# Sheet.net
KiCad netlist of a schematic drawn in Altium Designer
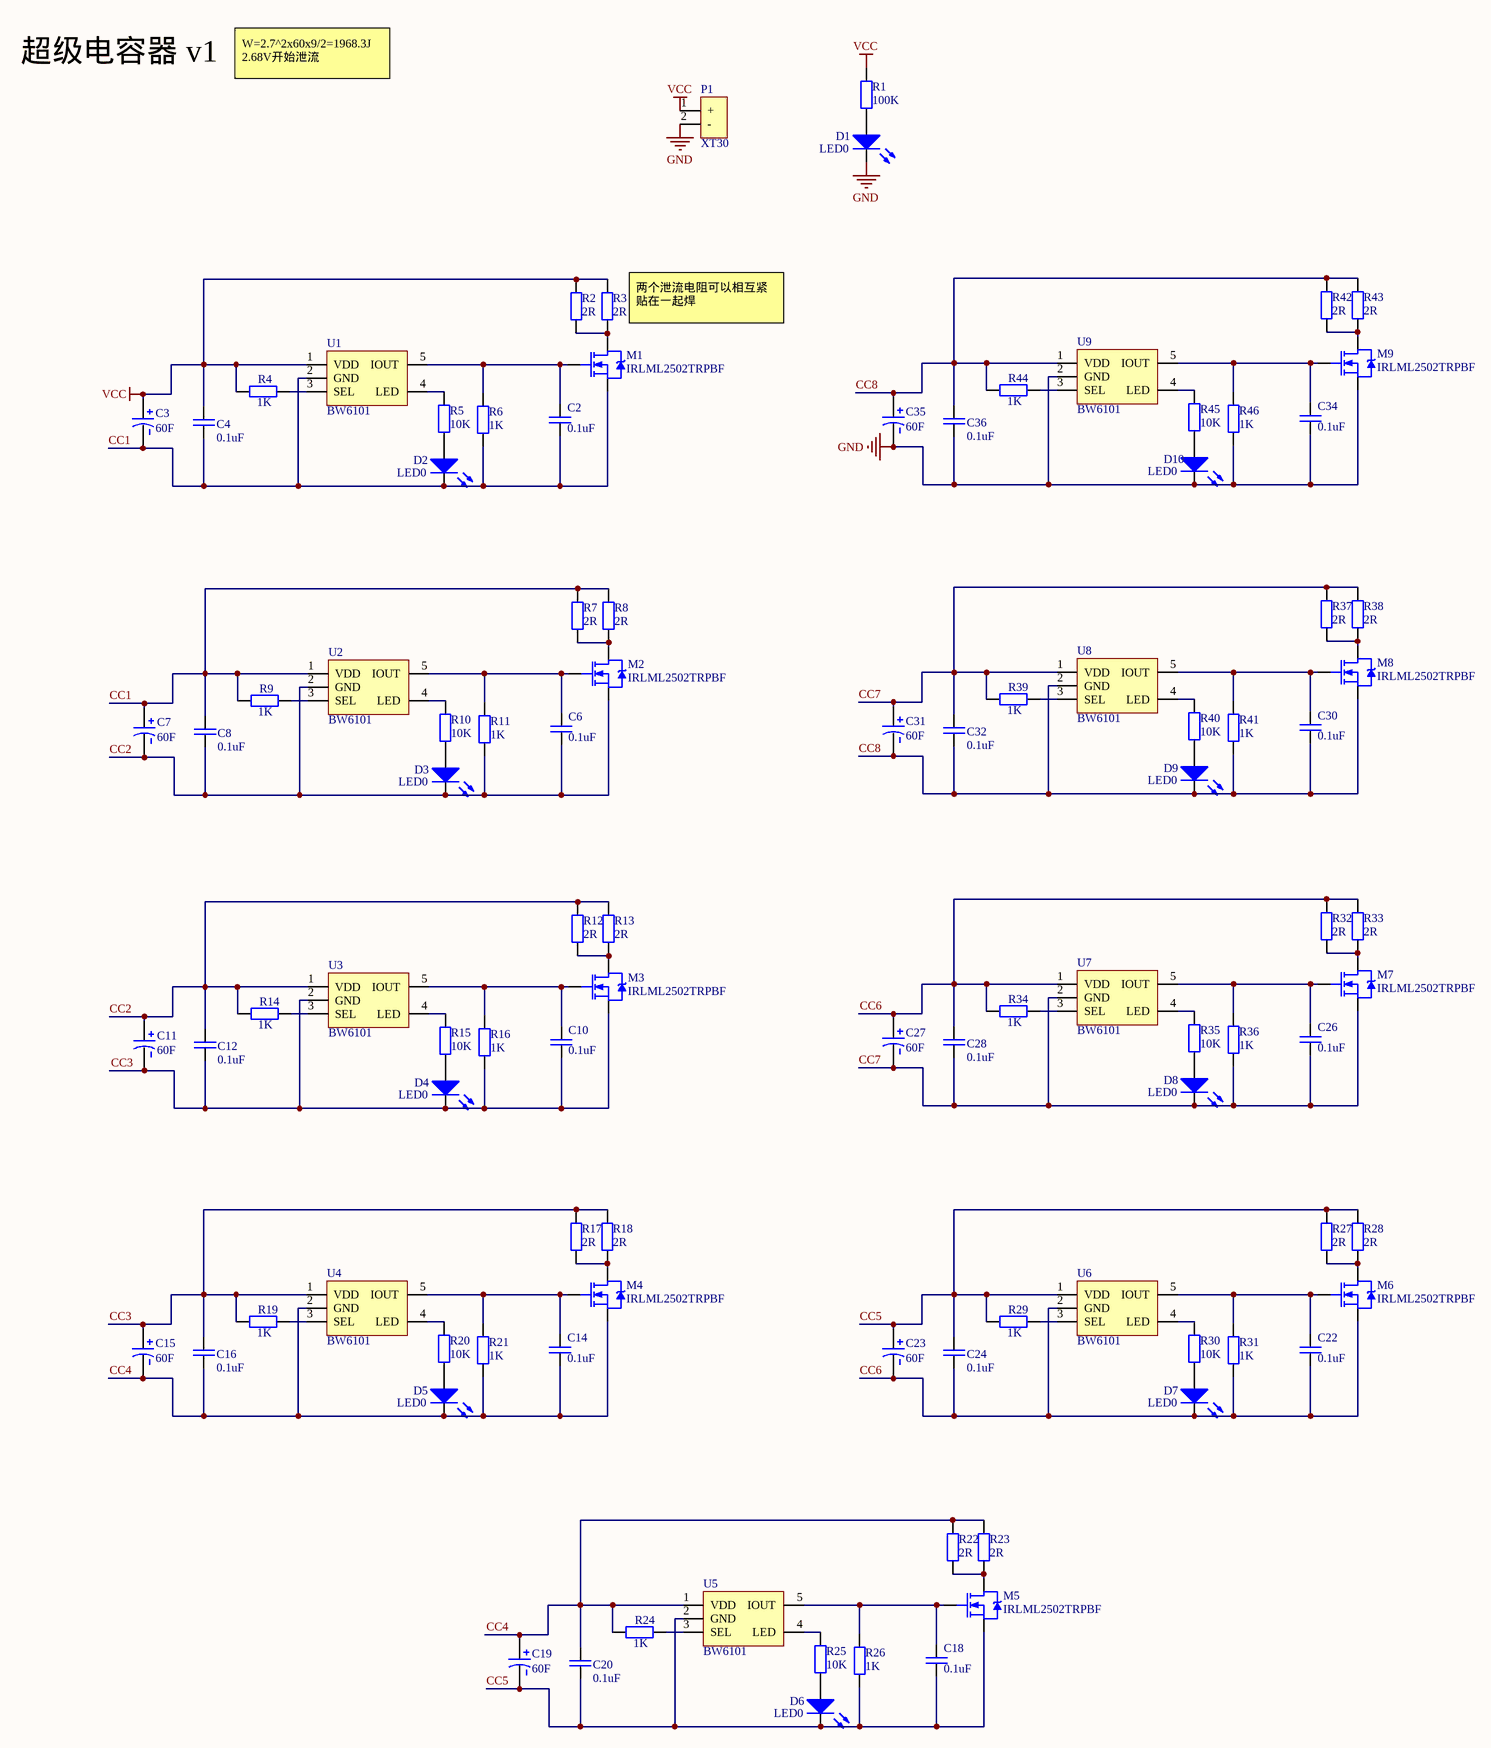
[diagram p0: Sheet.SchDoc]

(export (version "E")
  (design (tool "Eeschema 10.0.6"))
  (components
    (comp (ref "C2")
      (value "0.1uF")
      (footprint "0603_C")
      (fields (field (name "PUBLISHER") "Altium Limited"))
      (libsource (lib "电容-电阻-电感") (part "Cap"))
    )
    (comp (ref "C3") (value "60F") (footprint "18x40mm") (libsource (lib "电容-电阻-电感") (part "Super Cap")))
    (comp (ref "C4")
      (value "0.1uF")
      (footprint "0603_C")
      (fields (field (name "PUBLISHER") "Altium Limited"))
      (libsource (lib "电容-电阻-电感") (part "Cap"))
    )
    (comp (ref "C6")
      (value "0.1uF")
      (footprint "0603_C")
      (fields (field (name "PUBLISHER") "Altium Limited"))
      (libsource (lib "电容-电阻-电感") (part "Cap"))
    )
    (comp (ref "C7") (value "60F") (footprint "18x40mm") (libsource (lib "电容-电阻-电感") (part "Super Cap")))
    (comp (ref "C8")
      (value "0.1uF")
      (footprint "0603_C")
      (fields (field (name "PUBLISHER") "Altium Limited"))
      (libsource (lib "电容-电阻-电感") (part "Cap"))
    )
    (comp (ref "C10")
      (value "0.1uF")
      (footprint "0603_C")
      (fields (field (name "PUBLISHER") "Altium Limited"))
      (libsource (lib "电容-电阻-电感") (part "Cap"))
    )
    (comp (ref "C11") (value "60F") (footprint "18x40mm") (libsource (lib "电容-电阻-电感") (part "Super Cap")))
    (comp (ref "C12")
      (value "0.1uF")
      (footprint "0603_C")
      (fields (field (name "PUBLISHER") "Altium Limited"))
      (libsource (lib "电容-电阻-电感") (part "Cap"))
    )
    (comp (ref "C14")
      (value "0.1uF")
      (footprint "0603_C")
      (fields (field (name "PUBLISHER") "Altium Limited"))
      (libsource (lib "电容-电阻-电感") (part "Cap"))
    )
    (comp (ref "C15") (value "60F") (footprint "18x40mm") (libsource (lib "电容-电阻-电感") (part "Super Cap")))
    (comp (ref "C16")
      (value "0.1uF")
      (footprint "0603_C")
      (fields (field (name "PUBLISHER") "Altium Limited"))
      (libsource (lib "电容-电阻-电感") (part "Cap"))
    )
    (comp (ref "C18")
      (value "0.1uF")
      (footprint "0603_C")
      (fields (field (name "PUBLISHER") "Altium Limited"))
      (libsource (lib "电容-电阻-电感") (part "Cap"))
    )
    (comp (ref "C19") (value "60F") (footprint "18x40mm") (libsource (lib "电容-电阻-电感") (part "Super Cap")))
    (comp (ref "C20")
      (value "0.1uF")
      (footprint "0603_C")
      (fields (field (name "PUBLISHER") "Altium Limited"))
      (libsource (lib "电容-电阻-电感") (part "Cap"))
    )
    (comp (ref "C22")
      (value "0.1uF")
      (footprint "0603_C")
      (fields (field (name "PUBLISHER") "Altium Limited"))
      (libsource (lib "电容-电阻-电感") (part "Cap"))
    )
    (comp (ref "C23") (value "60F") (footprint "18x40mm") (libsource (lib "电容-电阻-电感") (part "Super Cap")))
    (comp (ref "C24")
      (value "0.1uF")
      (footprint "0603_C")
      (fields (field (name "PUBLISHER") "Altium Limited"))
      (libsource (lib "电容-电阻-电感") (part "Cap"))
    )
    (comp (ref "C26")
      (value "0.1uF")
      (footprint "0603_C")
      (fields (field (name "PUBLISHER") "Altium Limited"))
      (libsource (lib "电容-电阻-电感") (part "Cap"))
    )
    (comp (ref "C27") (value "60F") (footprint "18x40mm") (libsource (lib "电容-电阻-电感") (part "Super Cap")))
    (comp (ref "C28")
      (value "0.1uF")
      (footprint "0603_C")
      (fields (field (name "PUBLISHER") "Altium Limited"))
      (libsource (lib "电容-电阻-电感") (part "Cap"))
    )
    (comp (ref "C30")
      (value "0.1uF")
      (footprint "0603_C")
      (fields (field (name "PUBLISHER") "Altium Limited"))
      (libsource (lib "电容-电阻-电感") (part "Cap"))
    )
    (comp (ref "C31") (value "60F") (footprint "18x40mm") (libsource (lib "电容-电阻-电感") (part "Super Cap")))
    (comp (ref "C32")
      (value "0.1uF")
      (footprint "0603_C")
      (fields (field (name "PUBLISHER") "Altium Limited"))
      (libsource (lib "电容-电阻-电感") (part "Cap"))
    )
    (comp (ref "C34")
      (value "0.1uF")
      (footprint "0603_C")
      (fields (field (name "PUBLISHER") "Altium Limited"))
      (libsource (lib "电容-电阻-电感") (part "Cap"))
    )
    (comp (ref "C35") (value "60F") (footprint "18x40mm") (libsource (lib "电容-电阻-电感") (part "Super Cap")))
    (comp (ref "C36")
      (value "0.1uF")
      (footprint "0603_C")
      (fields (field (name "PUBLISHER") "Altium Limited"))
      (libsource (lib "电容-电阻-电感") (part "Cap"))
    )
    (comp (ref "D1")
      (value "LED0")
      (footprint "LED-0603")
      (description "发光二极管")
      (fields (field (name "PUBLISHER") "Altium Limited"))
      (libsource (lib "晶体管") (part "LED0"))
    )
    (comp (ref "D2")
      (value "LED0")
      (footprint "LED-0603")
      (description "发光二极管")
      (fields (field (name "PUBLISHER") "Altium Limited"))
      (libsource (lib "晶体管") (part "LED0"))
    )
    (comp (ref "D3")
      (value "LED0")
      (footprint "LED-0603")
      (description "发光二极管")
      (fields (field (name "PUBLISHER") "Altium Limited"))
      (libsource (lib "晶体管") (part "LED0"))
    )
    (comp (ref "D4")
      (value "LED0")
      (footprint "LED-0603")
      (description "发光二极管")
      (fields (field (name "PUBLISHER") "Altium Limited"))
      (libsource (lib "晶体管") (part "LED0"))
    )
    (comp (ref "D5")
      (value "LED0")
      (footprint "LED-0603")
      (description "发光二极管")
      (fields (field (name "PUBLISHER") "Altium Limited"))
      (libsource (lib "晶体管") (part "LED0"))
    )
    (comp (ref "D6")
      (value "LED0")
      (footprint "LED-0603")
      (description "发光二极管")
      (fields (field (name "PUBLISHER") "Altium Limited"))
      (libsource (lib "晶体管") (part "LED0"))
    )
    (comp (ref "D7")
      (value "LED0")
      (footprint "LED-0603")
      (description "发光二极管")
      (fields (field (name "PUBLISHER") "Altium Limited"))
      (libsource (lib "晶体管") (part "LED0"))
    )
    (comp (ref "D8")
      (value "LED0")
      (footprint "LED-0603")
      (description "发光二极管")
      (fields (field (name "PUBLISHER") "Altium Limited"))
      (libsource (lib "晶体管") (part "LED0"))
    )
    (comp (ref "D9")
      (value "LED0")
      (footprint "LED-0603")
      (description "发光二极管")
      (fields (field (name "PUBLISHER") "Altium Limited"))
      (libsource (lib "晶体管") (part "LED0"))
    )
    (comp (ref "D10")
      (value "LED0")
      (footprint "LED-0603")
      (description "发光二极管")
      (fields (field (name "PUBLISHER") "Altium Limited"))
      (libsource (lib "晶体管") (part "LED0"))
    )
    (comp (ref "M1")
      (value "IRLML2502TRPBF")
      (footprint "SOT_23 mos")
      (libsource (lib "晶体管") (part "MOSFET"))
    )
    (comp (ref "M2")
      (value "IRLML2502TRPBF")
      (footprint "SOT_23 mos")
      (libsource (lib "晶体管") (part "MOSFET"))
    )
    (comp (ref "M3")
      (value "IRLML2502TRPBF")
      (footprint "SOT_23 mos")
      (libsource (lib "晶体管") (part "MOSFET"))
    )
    (comp (ref "M4")
      (value "IRLML2502TRPBF")
      (footprint "SOT_23 mos")
      (libsource (lib "晶体管") (part "MOSFET"))
    )
    (comp (ref "M5")
      (value "IRLML2502TRPBF")
      (footprint "SOT_23 mos")
      (libsource (lib "晶体管") (part "MOSFET"))
    )
    (comp (ref "M6")
      (value "IRLML2502TRPBF")
      (footprint "SOT_23 mos")
      (libsource (lib "晶体管") (part "MOSFET"))
    )
    (comp (ref "M7")
      (value "IRLML2502TRPBF")
      (footprint "SOT_23 mos")
      (libsource (lib "晶体管") (part "MOSFET"))
    )
    (comp (ref "M8")
      (value "IRLML2502TRPBF")
      (footprint "SOT_23 mos")
      (libsource (lib "晶体管") (part "MOSFET"))
    )
    (comp (ref "M9")
      (value "IRLML2502TRPBF")
      (footprint "SOT_23 mos")
      (libsource (lib "晶体管") (part "MOSFET"))
    )
    (comp (ref "P1") (value "XT30") (footprint "XT30-F") (libsource (lib "连接器") (part "XT30")))
    (comp (ref "R1")
      (value "100K")
      (footprint "0603_R")
      (fields (field (name "PUBLISHER") "Altium Limited"))
      (libsource (lib "电容-电阻-电感") (part "Res"))
    )
    (comp (ref "R2")
      (value "2R")
      (footprint "2512_R")
      (fields (field (name "PUBLISHER") "Altium Limited"))
      (libsource (lib "电容-电阻-电感") (part "Res"))
    )
    (comp (ref "R3")
      (value "2R")
      (footprint "2512_R")
      (fields (field (name "PUBLISHER") "Altium Limited"))
      (libsource (lib "电容-电阻-电感") (part "Res"))
    )
    (comp (ref "R4")
      (value "1K")
      (footprint "0603_R")
      (fields (field (name "PUBLISHER") "Altium Limited"))
      (libsource (lib "") (part "Res_1"))
    )
    (comp (ref "R5")
      (value "10K")
      (footprint "0603_R")
      (fields (field (name "PUBLISHER") "Altium Limited"))
      (libsource (lib "电容-电阻-电感") (part "Res"))
    )
    (comp (ref "R6")
      (value "1K")
      (footprint "0603_R")
      (fields (field (name "PUBLISHER") "Altium Limited"))
      (libsource (lib "电容-电阻-电感") (part "Res"))
    )
    (comp (ref "R7")
      (value "2R")
      (footprint "2512_R")
      (fields (field (name "PUBLISHER") "Altium Limited"))
      (libsource (lib "电容-电阻-电感") (part "Res"))
    )
    (comp (ref "R8")
      (value "2R")
      (footprint "2512_R")
      (fields (field (name "PUBLISHER") "Altium Limited"))
      (libsource (lib "电容-电阻-电感") (part "Res"))
    )
    (comp (ref "R9")
      (value "1K")
      (footprint "0603_R")
      (fields (field (name "PUBLISHER") "Altium Limited"))
      (libsource (lib "") (part "Res_1"))
    )
    (comp (ref "R10")
      (value "10K")
      (footprint "0603_R")
      (fields (field (name "PUBLISHER") "Altium Limited"))
      (libsource (lib "电容-电阻-电感") (part "Res"))
    )
    (comp (ref "R11")
      (value "1K")
      (footprint "0603_R")
      (fields (field (name "PUBLISHER") "Altium Limited"))
      (libsource (lib "电容-电阻-电感") (part "Res"))
    )
    (comp (ref "R12")
      (value "2R")
      (footprint "2512_R")
      (fields (field (name "PUBLISHER") "Altium Limited"))
      (libsource (lib "电容-电阻-电感") (part "Res"))
    )
    (comp (ref "R13")
      (value "2R")
      (footprint "2512_R")
      (fields (field (name "PUBLISHER") "Altium Limited"))
      (libsource (lib "电容-电阻-电感") (part "Res"))
    )
    (comp (ref "R14")
      (value "1K")
      (footprint "0603_R")
      (fields (field (name "PUBLISHER") "Altium Limited"))
      (libsource (lib "") (part "Res_1"))
    )
    (comp (ref "R15")
      (value "10K")
      (footprint "0603_R")
      (fields (field (name "PUBLISHER") "Altium Limited"))
      (libsource (lib "电容-电阻-电感") (part "Res"))
    )
    (comp (ref "R16")
      (value "1K")
      (footprint "0603_R")
      (fields (field (name "PUBLISHER") "Altium Limited"))
      (libsource (lib "电容-电阻-电感") (part "Res"))
    )
    (comp (ref "R17")
      (value "2R")
      (footprint "2512_R")
      (fields (field (name "PUBLISHER") "Altium Limited"))
      (libsource (lib "电容-电阻-电感") (part "Res"))
    )
    (comp (ref "R18")
      (value "2R")
      (footprint "2512_R")
      (fields (field (name "PUBLISHER") "Altium Limited"))
      (libsource (lib "电容-电阻-电感") (part "Res"))
    )
    (comp (ref "R19")
      (value "1K")
      (footprint "0603_R")
      (fields (field (name "PUBLISHER") "Altium Limited"))
      (libsource (lib "") (part "Res_1"))
    )
    (comp (ref "R20")
      (value "10K")
      (footprint "0603_R")
      (fields (field (name "PUBLISHER") "Altium Limited"))
      (libsource (lib "电容-电阻-电感") (part "Res"))
    )
    (comp (ref "R21")
      (value "1K")
      (footprint "0603_R")
      (fields (field (name "PUBLISHER") "Altium Limited"))
      (libsource (lib "电容-电阻-电感") (part "Res"))
    )
    (comp (ref "R22")
      (value "2R")
      (footprint "2512_R")
      (fields (field (name "PUBLISHER") "Altium Limited"))
      (libsource (lib "电容-电阻-电感") (part "Res"))
    )
    (comp (ref "R23")
      (value "2R")
      (footprint "2512_R")
      (fields (field (name "PUBLISHER") "Altium Limited"))
      (libsource (lib "电容-电阻-电感") (part "Res"))
    )
    (comp (ref "R24")
      (value "1K")
      (footprint "0603_R")
      (fields (field (name "PUBLISHER") "Altium Limited"))
      (libsource (lib "") (part "Res_1"))
    )
    (comp (ref "R25")
      (value "10K")
      (footprint "0603_R")
      (fields (field (name "PUBLISHER") "Altium Limited"))
      (libsource (lib "电容-电阻-电感") (part "Res"))
    )
    (comp (ref "R26")
      (value "1K")
      (footprint "0603_R")
      (fields (field (name "PUBLISHER") "Altium Limited"))
      (libsource (lib "电容-电阻-电感") (part "Res"))
    )
    (comp (ref "R27")
      (value "2R")
      (footprint "2512_R")
      (fields (field (name "PUBLISHER") "Altium Limited"))
      (libsource (lib "电容-电阻-电感") (part "Res"))
    )
    (comp (ref "R28")
      (value "2R")
      (footprint "2512_R")
      (fields (field (name "PUBLISHER") "Altium Limited"))
      (libsource (lib "电容-电阻-电感") (part "Res"))
    )
    (comp (ref "R29")
      (value "1K")
      (footprint "0603_R")
      (fields (field (name "PUBLISHER") "Altium Limited"))
      (libsource (lib "") (part "Res_1"))
    )
    (comp (ref "R30")
      (value "10K")
      (footprint "0603_R")
      (fields (field (name "PUBLISHER") "Altium Limited"))
      (libsource (lib "电容-电阻-电感") (part "Res"))
    )
    (comp (ref "R31")
      (value "1K")
      (footprint "0603_R")
      (fields (field (name "PUBLISHER") "Altium Limited"))
      (libsource (lib "电容-电阻-电感") (part "Res"))
    )
    (comp (ref "R32")
      (value "2R")
      (footprint "2512_R")
      (fields (field (name "PUBLISHER") "Altium Limited"))
      (libsource (lib "电容-电阻-电感") (part "Res"))
    )
    (comp (ref "R33")
      (value "2R")
      (footprint "2512_R")
      (fields (field (name "PUBLISHER") "Altium Limited"))
      (libsource (lib "电容-电阻-电感") (part "Res"))
    )
    (comp (ref "R34")
      (value "1K")
      (footprint "0603_R")
      (fields (field (name "PUBLISHER") "Altium Limited"))
      (libsource (lib "") (part "Res_1"))
    )
    (comp (ref "R35")
      (value "10K")
      (footprint "0603_R")
      (fields (field (name "PUBLISHER") "Altium Limited"))
      (libsource (lib "电容-电阻-电感") (part "Res"))
    )
    (comp (ref "R36")
      (value "1K")
      (footprint "0603_R")
      (fields (field (name "PUBLISHER") "Altium Limited"))
      (libsource (lib "电容-电阻-电感") (part "Res"))
    )
    (comp (ref "R37")
      (value "2R")
      (footprint "2512_R")
      (fields (field (name "PUBLISHER") "Altium Limited"))
      (libsource (lib "电容-电阻-电感") (part "Res"))
    )
    (comp (ref "R38")
      (value "2R")
      (footprint "2512_R")
      (fields (field (name "PUBLISHER") "Altium Limited"))
      (libsource (lib "电容-电阻-电感") (part "Res"))
    )
    (comp (ref "R39")
      (value "1K")
      (footprint "0603_R")
      (fields (field (name "PUBLISHER") "Altium Limited"))
      (libsource (lib "") (part "Res_1"))
    )
    (comp (ref "R40")
      (value "10K")
      (footprint "0603_R")
      (fields (field (name "PUBLISHER") "Altium Limited"))
      (libsource (lib "电容-电阻-电感") (part "Res"))
    )
    (comp (ref "R41")
      (value "1K")
      (footprint "0603_R")
      (fields (field (name "PUBLISHER") "Altium Limited"))
      (libsource (lib "电容-电阻-电感") (part "Res"))
    )
    (comp (ref "R42")
      (value "2R")
      (footprint "2512_R")
      (fields (field (name "PUBLISHER") "Altium Limited"))
      (libsource (lib "电容-电阻-电感") (part "Res"))
    )
    (comp (ref "R43")
      (value "2R")
      (footprint "2512_R")
      (fields (field (name "PUBLISHER") "Altium Limited"))
      (libsource (lib "电容-电阻-电感") (part "Res"))
    )
    (comp (ref "R44")
      (value "1K")
      (footprint "0603_R")
      (fields (field (name "PUBLISHER") "Altium Limited"))
      (libsource (lib "") (part "Res_1"))
    )
    (comp (ref "R45")
      (value "10K")
      (footprint "0603_R")
      (fields (field (name "PUBLISHER") "Altium Limited"))
      (libsource (lib "电容-电阻-电感") (part "Res"))
    )
    (comp (ref "R46")
      (value "1K")
      (footprint "0603_R")
      (fields (field (name "PUBLISHER") "Altium Limited"))
      (libsource (lib "电容-电阻-电感") (part "Res"))
    )
    (comp (ref "U1") (value "BW6101") (footprint "SOT23-5") (libsource (lib "Super Cap") (part "BW6101")))
    (comp (ref "U2") (value "BW6101") (footprint "SOT23-5") (libsource (lib "Super Cap") (part "BW6101")))
    (comp (ref "U3") (value "BW6101") (footprint "SOT23-5") (libsource (lib "Super Cap") (part "BW6101")))
    (comp (ref "U4") (value "BW6101") (footprint "SOT23-5") (libsource (lib "Super Cap") (part "BW6101")))
    (comp (ref "U5") (value "BW6101") (footprint "SOT23-5") (libsource (lib "Super Cap") (part "BW6101")))
    (comp (ref "U6") (value "BW6101") (footprint "SOT23-5") (libsource (lib "Super Cap") (part "BW6101")))
    (comp (ref "U7") (value "BW6101") (footprint "SOT23-5") (libsource (lib "Super Cap") (part "BW6101")))
    (comp (ref "U8") (value "BW6101") (footprint "SOT23-5") (libsource (lib "Super Cap") (part "BW6101")))
    (comp (ref "U9") (value "BW6101") (footprint "SOT23-5") (libsource (lib "Super Cap") (part "BW6101")))
  )
  (nets
    (net (code "1") (name "/CC1") (class "Default")
      (node (ref "C2") (pin "1") (pinfunction "1_1") (pintype "passive"))
      (node (ref "C3") (pin "2") (pinfunction "2_2") (pintype "passive"))
      (node (ref "C4") (pin "1") (pinfunction "1_1") (pintype "passive"))
      (node (ref "C7") (pin "1") (pinfunction "1_1") (pintype "passive"))
      (node (ref "C8") (pin "2") (pinfunction "2_2") (pintype "passive"))
      (node (ref "D2") (pin "2") (pinfunction "K_2") (pintype "passive"))
      (node (ref "M1") (pin "S") (pinfunction "S_S") (pintype "passive"))
      (node (ref "R6") (pin "1") (pinfunction "1_1") (pintype "passive"))
      (node (ref "R7") (pin "2") (pinfunction "2_2") (pintype "passive"))
      (node (ref "R8") (pin "2") (pinfunction "2_2") (pintype "passive"))
      (node (ref "R9") (pin "2") (pinfunction "2_2") (pintype "passive"))
      (node (ref "U1") (pin "2") (pinfunction "GND_2") (pintype "power_in"))
      (node (ref "U2") (pin "1") (pinfunction "VDD_1") (pintype "power_in"))
    )
    (net (code "2") (name "/CC2") (class "Default")
      (node (ref "C11") (pin "1") (pinfunction "1_1") (pintype "passive"))
      (node (ref "C12") (pin "2") (pinfunction "2_2") (pintype "passive"))
      (node (ref "C6") (pin "1") (pinfunction "1_1") (pintype "passive"))
      (node (ref "C7") (pin "2") (pinfunction "2_2") (pintype "passive"))
      (node (ref "C8") (pin "1") (pinfunction "1_1") (pintype "passive"))
      (node (ref "D3") (pin "2") (pinfunction "K_2") (pintype "passive"))
      (node (ref "M2") (pin "S") (pinfunction "S_S") (pintype "passive"))
      (node (ref "R11") (pin "1") (pinfunction "1_1") (pintype "passive"))
      (node (ref "R12") (pin "2") (pinfunction "2_2") (pintype "passive"))
      (node (ref "R13") (pin "2") (pinfunction "2_2") (pintype "passive"))
      (node (ref "R14") (pin "2") (pinfunction "2_2") (pintype "passive"))
      (node (ref "U2") (pin "2") (pinfunction "GND_2") (pintype "power_in"))
      (node (ref "U3") (pin "1") (pinfunction "VDD_1") (pintype "power_in"))
    )
    (net (code "3") (name "/CC3") (class "Default")
      (node (ref "C10") (pin "1") (pinfunction "1_1") (pintype "passive"))
      (node (ref "C11") (pin "2") (pinfunction "2_2") (pintype "passive"))
      (node (ref "C12") (pin "1") (pinfunction "1_1") (pintype "passive"))
      (node (ref "C15") (pin "1") (pinfunction "1_1") (pintype "passive"))
      (node (ref "C16") (pin "2") (pinfunction "2_2") (pintype "passive"))
      (node (ref "D4") (pin "2") (pinfunction "K_2") (pintype "passive"))
      (node (ref "M3") (pin "S") (pinfunction "S_S") (pintype "passive"))
      (node (ref "R16") (pin "1") (pinfunction "1_1") (pintype "passive"))
      (node (ref "R17") (pin "2") (pinfunction "2_2") (pintype "passive"))
      (node (ref "R18") (pin "2") (pinfunction "2_2") (pintype "passive"))
      (node (ref "R19") (pin "2") (pinfunction "2_2") (pintype "passive"))
      (node (ref "U3") (pin "2") (pinfunction "GND_2") (pintype "power_in"))
      (node (ref "U4") (pin "1") (pinfunction "VDD_1") (pintype "power_in"))
    )
    (net (code "4") (name "/CC4") (class "Default")
      (node (ref "C14") (pin "1") (pinfunction "1_1") (pintype "passive"))
      (node (ref "C15") (pin "2") (pinfunction "2_2") (pintype "passive"))
      (node (ref "C16") (pin "1") (pinfunction "1_1") (pintype "passive"))
      (node (ref "C19") (pin "1") (pinfunction "1_1") (pintype "passive"))
      (node (ref "C20") (pin "2") (pinfunction "2_2") (pintype "passive"))
      (node (ref "D5") (pin "2") (pinfunction "K_2") (pintype "passive"))
      (node (ref "M4") (pin "S") (pinfunction "S_S") (pintype "passive"))
      (node (ref "R21") (pin "1") (pinfunction "1_1") (pintype "passive"))
      (node (ref "R22") (pin "2") (pinfunction "2_2") (pintype "passive"))
      (node (ref "R23") (pin "2") (pinfunction "2_2") (pintype "passive"))
      (node (ref "R24") (pin "2") (pinfunction "2_2") (pintype "passive"))
      (node (ref "U4") (pin "2") (pinfunction "GND_2") (pintype "power_in"))
      (node (ref "U5") (pin "1") (pinfunction "VDD_1") (pintype "power_in"))
    )
    (net (code "5") (name "/CC5") (class "Default")
      (node (ref "C18") (pin "1") (pinfunction "1_1") (pintype "passive"))
      (node (ref "C19") (pin "2") (pinfunction "2_2") (pintype "passive"))
      (node (ref "C20") (pin "1") (pinfunction "1_1") (pintype "passive"))
      (node (ref "C23") (pin "1") (pinfunction "1_1") (pintype "passive"))
      (node (ref "C24") (pin "2") (pinfunction "2_2") (pintype "passive"))
      (node (ref "D6") (pin "2") (pinfunction "K_2") (pintype "passive"))
      (node (ref "M5") (pin "S") (pinfunction "S_S") (pintype "passive"))
      (node (ref "R26") (pin "1") (pinfunction "1_1") (pintype "passive"))
      (node (ref "R27") (pin "2") (pinfunction "2_2") (pintype "passive"))
      (node (ref "R28") (pin "2") (pinfunction "2_2") (pintype "passive"))
      (node (ref "R29") (pin "2") (pinfunction "2_2") (pintype "passive"))
      (node (ref "U5") (pin "2") (pinfunction "GND_2") (pintype "power_in"))
      (node (ref "U6") (pin "1") (pinfunction "VDD_1") (pintype "power_in"))
    )
    (net (code "6") (name "/CC6") (class "Default")
      (node (ref "C22") (pin "1") (pinfunction "1_1") (pintype "passive"))
      (node (ref "C23") (pin "2") (pinfunction "2_2") (pintype "passive"))
      (node (ref "C24") (pin "1") (pinfunction "1_1") (pintype "passive"))
      (node (ref "C27") (pin "1") (pinfunction "1_1") (pintype "passive"))
      (node (ref "C28") (pin "2") (pinfunction "2_2") (pintype "passive"))
      (node (ref "D7") (pin "2") (pinfunction "K_2") (pintype "passive"))
      (node (ref "M6") (pin "S") (pinfunction "S_S") (pintype "passive"))
      (node (ref "R31") (pin "1") (pinfunction "1_1") (pintype "passive"))
      (node (ref "R32") (pin "2") (pinfunction "2_2") (pintype "passive"))
      (node (ref "R33") (pin "2") (pinfunction "2_2") (pintype "passive"))
      (node (ref "R34") (pin "2") (pinfunction "2_2") (pintype "passive"))
      (node (ref "U6") (pin "2") (pinfunction "GND_2") (pintype "power_in"))
      (node (ref "U7") (pin "1") (pinfunction "VDD_1") (pintype "power_in"))
    )
    (net (code "7") (name "/CC7") (class "Default")
      (node (ref "C26") (pin "1") (pinfunction "1_1") (pintype "passive"))
      (node (ref "C27") (pin "2") (pinfunction "2_2") (pintype "passive"))
      (node (ref "C28") (pin "1") (pinfunction "1_1") (pintype "passive"))
      (node (ref "C31") (pin "1") (pinfunction "1_1") (pintype "passive"))
      (node (ref "C32") (pin "2") (pinfunction "2_2") (pintype "passive"))
      (node (ref "D8") (pin "2") (pinfunction "K_2") (pintype "passive"))
      (node (ref "M7") (pin "S") (pinfunction "S_S") (pintype "passive"))
      (node (ref "R36") (pin "1") (pinfunction "1_1") (pintype "passive"))
      (node (ref "R37") (pin "2") (pinfunction "2_2") (pintype "passive"))
      (node (ref "R38") (pin "2") (pinfunction "2_2") (pintype "passive"))
      (node (ref "R39") (pin "2") (pinfunction "2_2") (pintype "passive"))
      (node (ref "U7") (pin "2") (pinfunction "GND_2") (pintype "power_in"))
      (node (ref "U8") (pin "1") (pinfunction "VDD_1") (pintype "power_in"))
    )
    (net (code "8") (name "/CC8") (class "Default")
      (node (ref "C30") (pin "1") (pinfunction "1_1") (pintype "passive"))
      (node (ref "C31") (pin "2") (pinfunction "2_2") (pintype "passive"))
      (node (ref "C32") (pin "1") (pinfunction "1_1") (pintype "passive"))
      (node (ref "C35") (pin "1") (pinfunction "1_1") (pintype "passive"))
      (node (ref "C36") (pin "2") (pinfunction "2_2") (pintype "passive"))
      (node (ref "D9") (pin "2") (pinfunction "K_2") (pintype "passive"))
      (node (ref "M8") (pin "S") (pinfunction "S_S") (pintype "passive"))
      (node (ref "R41") (pin "1") (pinfunction "1_1") (pintype "passive"))
      (node (ref "R42") (pin "2") (pinfunction "2_2") (pintype "passive"))
      (node (ref "R43") (pin "2") (pinfunction "2_2") (pintype "passive"))
      (node (ref "R44") (pin "2") (pinfunction "2_2") (pintype "passive"))
      (node (ref "U8") (pin "2") (pinfunction "GND_2") (pintype "power_in"))
      (node (ref "U9") (pin "1") (pinfunction "VDD_1") (pintype "power_in"))
    )
    (net (code "9") (name "GND") (class "Default")
      (node (ref "C34") (pin "1") (pinfunction "1_1") (pintype "passive"))
      (node (ref "C35") (pin "2") (pinfunction "2_2") (pintype "passive"))
      (node (ref "C36") (pin "1") (pinfunction "1_1") (pintype "passive"))
      (node (ref "D1") (pin "2") (pinfunction "K_2") (pintype "passive"))
      (node (ref "D10") (pin "2") (pinfunction "K_2") (pintype "passive"))
      (node (ref "M9") (pin "S") (pinfunction "S_S") (pintype "passive"))
      (node (ref "P1") (pin "2") (pinfunction "-_2") (pintype "passive"))
      (node (ref "R46") (pin "1") (pinfunction "1_1") (pintype "passive"))
      (node (ref "U9") (pin "2") (pinfunction "GND_2") (pintype "power_in"))
    )
    (net (code "10") (name "Net-(D1-A)") (class "Default")
      (node (ref "D1") (pin "1") (pinfunction "A_1") (pintype "passive"))
      (node (ref "R1") (pin "1") (pinfunction "1_1") (pintype "passive"))
    )
    (net (code "11") (name "Net-(D2-A)") (class "Default")
      (node (ref "D2") (pin "1") (pinfunction "A_1") (pintype "passive"))
      (node (ref "R5") (pin "1") (pinfunction "1_1") (pintype "passive"))
    )
    (net (code "12") (name "Net-(D3-A)") (class "Default")
      (node (ref "D3") (pin "1") (pinfunction "A_1") (pintype "passive"))
      (node (ref "R10") (pin "1") (pinfunction "1_1") (pintype "passive"))
    )
    (net (code "13") (name "Net-(D4-A)") (class "Default")
      (node (ref "D4") (pin "1") (pinfunction "A_1") (pintype "passive"))
      (node (ref "R15") (pin "1") (pinfunction "1_1") (pintype "passive"))
    )
    (net (code "14") (name "Net-(D5-A)") (class "Default")
      (node (ref "D5") (pin "1") (pinfunction "A_1") (pintype "passive"))
      (node (ref "R20") (pin "1") (pinfunction "1_1") (pintype "passive"))
    )
    (net (code "15") (name "Net-(D6-A)") (class "Default")
      (node (ref "D6") (pin "1") (pinfunction "A_1") (pintype "passive"))
      (node (ref "R25") (pin "1") (pinfunction "1_1") (pintype "passive"))
    )
    (net (code "16") (name "Net-(D7-A)") (class "Default")
      (node (ref "D7") (pin "1") (pinfunction "A_1") (pintype "passive"))
      (node (ref "R30") (pin "1") (pinfunction "1_1") (pintype "passive"))
    )
    (net (code "17") (name "Net-(D8-A)") (class "Default")
      (node (ref "D8") (pin "1") (pinfunction "A_1") (pintype "passive"))
      (node (ref "R35") (pin "1") (pinfunction "1_1") (pintype "passive"))
    )
    (net (code "18") (name "Net-(D9-A)") (class "Default")
      (node (ref "D9") (pin "1") (pinfunction "A_1") (pintype "passive"))
      (node (ref "R40") (pin "1") (pinfunction "1_1") (pintype "passive"))
    )
    (net (code "19") (name "Net-(D10-A)") (class "Default")
      (node (ref "D10") (pin "1") (pinfunction "A_1") (pintype "passive"))
      (node (ref "R45") (pin "1") (pinfunction "1_1") (pintype "passive"))
    )
    (net (code "20") (name "Net-(M1-PadD)") (class "Default")
      (node (ref "M1") (pin "D") (pinfunction "D_D") (pintype "passive"))
      (node (ref "R2") (pin "1") (pinfunction "1_1") (pintype "passive"))
      (node (ref "R3") (pin "1") (pinfunction "1_1") (pintype "passive"))
    )
    (net (code "21") (name "Net-(M2-PadD)") (class "Default")
      (node (ref "M2") (pin "D") (pinfunction "D_D") (pintype "passive"))
      (node (ref "R7") (pin "1") (pinfunction "1_1") (pintype "passive"))
      (node (ref "R8") (pin "1") (pinfunction "1_1") (pintype "passive"))
    )
    (net (code "22") (name "Net-(M3-PadD)") (class "Default")
      (node (ref "M3") (pin "D") (pinfunction "D_D") (pintype "passive"))
      (node (ref "R12") (pin "1") (pinfunction "1_1") (pintype "passive"))
      (node (ref "R13") (pin "1") (pinfunction "1_1") (pintype "passive"))
    )
    (net (code "23") (name "Net-(M4-PadD)") (class "Default")
      (node (ref "M4") (pin "D") (pinfunction "D_D") (pintype "passive"))
      (node (ref "R17") (pin "1") (pinfunction "1_1") (pintype "passive"))
      (node (ref "R18") (pin "1") (pinfunction "1_1") (pintype "passive"))
    )
    (net (code "24") (name "Net-(M5-PadD)") (class "Default")
      (node (ref "M5") (pin "D") (pinfunction "D_D") (pintype "passive"))
      (node (ref "R22") (pin "1") (pinfunction "1_1") (pintype "passive"))
      (node (ref "R23") (pin "1") (pinfunction "1_1") (pintype "passive"))
    )
    (net (code "25") (name "Net-(M6-PadD)") (class "Default")
      (node (ref "M6") (pin "D") (pinfunction "D_D") (pintype "passive"))
      (node (ref "R27") (pin "1") (pinfunction "1_1") (pintype "passive"))
      (node (ref "R28") (pin "1") (pinfunction "1_1") (pintype "passive"))
    )
    (net (code "26") (name "Net-(M7-PadD)") (class "Default")
      (node (ref "M7") (pin "D") (pinfunction "D_D") (pintype "passive"))
      (node (ref "R32") (pin "1") (pinfunction "1_1") (pintype "passive"))
      (node (ref "R33") (pin "1") (pinfunction "1_1") (pintype "passive"))
    )
    (net (code "27") (name "Net-(M8-PadD)") (class "Default")
      (node (ref "M8") (pin "D") (pinfunction "D_D") (pintype "passive"))
      (node (ref "R37") (pin "1") (pinfunction "1_1") (pintype "passive"))
      (node (ref "R38") (pin "1") (pinfunction "1_1") (pintype "passive"))
    )
    (net (code "28") (name "Net-(M9-PadD)") (class "Default")
      (node (ref "M9") (pin "D") (pinfunction "D_D") (pintype "passive"))
      (node (ref "R42") (pin "1") (pinfunction "1_1") (pintype "passive"))
      (node (ref "R43") (pin "1") (pinfunction "1_1") (pintype "passive"))
    )
    (net (code "29") (name "Net-(U1-IOUT)") (class "Default")
      (node (ref "C2") (pin "2") (pinfunction "2_2") (pintype "passive"))
      (node (ref "M1") (pin "G") (pinfunction "G_G") (pintype "passive"))
      (node (ref "R6") (pin "2") (pinfunction "2_2") (pintype "passive"))
      (node (ref "U1") (pin "5") (pinfunction "IOUT_5") (pintype "power_in"))
    )
    (net (code "30") (name "Net-(U1-LED)") (class "Default")
      (node (ref "R5") (pin "2") (pinfunction "2_2") (pintype "passive"))
      (node (ref "U1") (pin "4") (pinfunction "LED_4") (pintype "power_in"))
    )
    (net (code "31") (name "Net-(U1-SEL)") (class "Default")
      (node (ref "R4") (pin "1") (pinfunction "1_1") (pintype "passive"))
      (node (ref "U1") (pin "3") (pinfunction "SEL_3") (pintype "power_in"))
    )
    (net (code "32") (name "Net-(U2-IOUT)") (class "Default")
      (node (ref "C6") (pin "2") (pinfunction "2_2") (pintype "passive"))
      (node (ref "M2") (pin "G") (pinfunction "G_G") (pintype "passive"))
      (node (ref "R11") (pin "2") (pinfunction "2_2") (pintype "passive"))
      (node (ref "U2") (pin "5") (pinfunction "IOUT_5") (pintype "power_in"))
    )
    (net (code "33") (name "Net-(U2-LED)") (class "Default")
      (node (ref "R10") (pin "2") (pinfunction "2_2") (pintype "passive"))
      (node (ref "U2") (pin "4") (pinfunction "LED_4") (pintype "power_in"))
    )
    (net (code "34") (name "Net-(U2-SEL)") (class "Default")
      (node (ref "R9") (pin "1") (pinfunction "1_1") (pintype "passive"))
      (node (ref "U2") (pin "3") (pinfunction "SEL_3") (pintype "power_in"))
    )
    (net (code "35") (name "Net-(U3-IOUT)") (class "Default")
      (node (ref "C10") (pin "2") (pinfunction "2_2") (pintype "passive"))
      (node (ref "M3") (pin "G") (pinfunction "G_G") (pintype "passive"))
      (node (ref "R16") (pin "2") (pinfunction "2_2") (pintype "passive"))
      (node (ref "U3") (pin "5") (pinfunction "IOUT_5") (pintype "power_in"))
    )
    (net (code "36") (name "Net-(U3-LED)") (class "Default")
      (node (ref "R15") (pin "2") (pinfunction "2_2") (pintype "passive"))
      (node (ref "U3") (pin "4") (pinfunction "LED_4") (pintype "power_in"))
    )
    (net (code "37") (name "Net-(U3-SEL)") (class "Default")
      (node (ref "R14") (pin "1") (pinfunction "1_1") (pintype "passive"))
      (node (ref "U3") (pin "3") (pinfunction "SEL_3") (pintype "power_in"))
    )
    (net (code "38") (name "Net-(U4-IOUT)") (class "Default")
      (node (ref "C14") (pin "2") (pinfunction "2_2") (pintype "passive"))
      (node (ref "M4") (pin "G") (pinfunction "G_G") (pintype "passive"))
      (node (ref "R21") (pin "2") (pinfunction "2_2") (pintype "passive"))
      (node (ref "U4") (pin "5") (pinfunction "IOUT_5") (pintype "power_in"))
    )
    (net (code "39") (name "Net-(U4-LED)") (class "Default")
      (node (ref "R20") (pin "2") (pinfunction "2_2") (pintype "passive"))
      (node (ref "U4") (pin "4") (pinfunction "LED_4") (pintype "power_in"))
    )
    (net (code "40") (name "Net-(U4-SEL)") (class "Default")
      (node (ref "R19") (pin "1") (pinfunction "1_1") (pintype "passive"))
      (node (ref "U4") (pin "3") (pinfunction "SEL_3") (pintype "power_in"))
    )
    (net (code "41") (name "Net-(U5-IOUT)") (class "Default")
      (node (ref "C18") (pin "2") (pinfunction "2_2") (pintype "passive"))
      (node (ref "M5") (pin "G") (pinfunction "G_G") (pintype "passive"))
      (node (ref "R26") (pin "2") (pinfunction "2_2") (pintype "passive"))
      (node (ref "U5") (pin "5") (pinfunction "IOUT_5") (pintype "power_in"))
    )
    (net (code "42") (name "Net-(U5-LED)") (class "Default")
      (node (ref "R25") (pin "2") (pinfunction "2_2") (pintype "passive"))
      (node (ref "U5") (pin "4") (pinfunction "LED_4") (pintype "power_in"))
    )
    (net (code "43") (name "Net-(U5-SEL)") (class "Default")
      (node (ref "R24") (pin "1") (pinfunction "1_1") (pintype "passive"))
      (node (ref "U5") (pin "3") (pinfunction "SEL_3") (pintype "power_in"))
    )
    (net (code "44") (name "Net-(U6-IOUT)") (class "Default")
      (node (ref "C22") (pin "2") (pinfunction "2_2") (pintype "passive"))
      (node (ref "M6") (pin "G") (pinfunction "G_G") (pintype "passive"))
      (node (ref "R31") (pin "2") (pinfunction "2_2") (pintype "passive"))
      (node (ref "U6") (pin "5") (pinfunction "IOUT_5") (pintype "power_in"))
    )
    (net (code "45") (name "Net-(U6-LED)") (class "Default")
      (node (ref "R30") (pin "2") (pinfunction "2_2") (pintype "passive"))
      (node (ref "U6") (pin "4") (pinfunction "LED_4") (pintype "power_in"))
    )
    (net (code "46") (name "Net-(U6-SEL)") (class "Default")
      (node (ref "R29") (pin "1") (pinfunction "1_1") (pintype "passive"))
      (node (ref "U6") (pin "3") (pinfunction "SEL_3") (pintype "power_in"))
    )
    (net (code "47") (name "Net-(U7-IOUT)") (class "Default")
      (node (ref "C26") (pin "2") (pinfunction "2_2") (pintype "passive"))
      (node (ref "M7") (pin "G") (pinfunction "G_G") (pintype "passive"))
      (node (ref "R36") (pin "2") (pinfunction "2_2") (pintype "passive"))
      (node (ref "U7") (pin "5") (pinfunction "IOUT_5") (pintype "power_in"))
    )
    (net (code "48") (name "Net-(U7-LED)") (class "Default")
      (node (ref "R35") (pin "2") (pinfunction "2_2") (pintype "passive"))
      (node (ref "U7") (pin "4") (pinfunction "LED_4") (pintype "power_in"))
    )
    (net (code "49") (name "Net-(U7-SEL)") (class "Default")
      (node (ref "R34") (pin "1") (pinfunction "1_1") (pintype "passive"))
      (node (ref "U7") (pin "3") (pinfunction "SEL_3") (pintype "power_in"))
    )
    (net (code "50") (name "Net-(U8-IOUT)") (class "Default")
      (node (ref "C30") (pin "2") (pinfunction "2_2") (pintype "passive"))
      (node (ref "M8") (pin "G") (pinfunction "G_G") (pintype "passive"))
      (node (ref "R41") (pin "2") (pinfunction "2_2") (pintype "passive"))
      (node (ref "U8") (pin "5") (pinfunction "IOUT_5") (pintype "power_in"))
    )
    (net (code "51") (name "Net-(U8-LED)") (class "Default")
      (node (ref "R40") (pin "2") (pinfunction "2_2") (pintype "passive"))
      (node (ref "U8") (pin "4") (pinfunction "LED_4") (pintype "power_in"))
    )
    (net (code "52") (name "Net-(U8-SEL)") (class "Default")
      (node (ref "R39") (pin "1") (pinfunction "1_1") (pintype "passive"))
      (node (ref "U8") (pin "3") (pinfunction "SEL_3") (pintype "power_in"))
    )
    (net (code "53") (name "Net-(U9-IOUT)") (class "Default")
      (node (ref "C34") (pin "2") (pinfunction "2_2") (pintype "passive"))
      (node (ref "M9") (pin "G") (pinfunction "G_G") (pintype "passive"))
      (node (ref "R46") (pin "2") (pinfunction "2_2") (pintype "passive"))
      (node (ref "U9") (pin "5") (pinfunction "IOUT_5") (pintype "power_in"))
    )
    (net (code "54") (name "Net-(U9-LED)") (class "Default")
      (node (ref "R45") (pin "2") (pinfunction "2_2") (pintype "passive"))
      (node (ref "U9") (pin "4") (pinfunction "LED_4") (pintype "power_in"))
    )
    (net (code "55") (name "Net-(U9-SEL)") (class "Default")
      (node (ref "R44") (pin "1") (pinfunction "1_1") (pintype "passive"))
      (node (ref "U9") (pin "3") (pinfunction "SEL_3") (pintype "power_in"))
    )
    (net (code "56") (name "VCC") (class "Default")
      (node (ref "C3") (pin "1") (pinfunction "1_1") (pintype "passive"))
      (node (ref "C4") (pin "2") (pinfunction "2_2") (pintype "passive"))
      (node (ref "P1") (pin "1") (pinfunction "+_1") (pintype "passive"))
      (node (ref "R1") (pin "2") (pinfunction "2_2") (pintype "passive"))
      (node (ref "R2") (pin "2") (pinfunction "2_2") (pintype "passive"))
      (node (ref "R3") (pin "2") (pinfunction "2_2") (pintype "passive"))
      (node (ref "R4") (pin "2") (pinfunction "2_2") (pintype "passive"))
      (node (ref "U1") (pin "1") (pinfunction "VDD_1") (pintype "power_in"))
    )
  )
)
